# Drive.net
KiCad netlist of a schematic drawn in Altium Designer
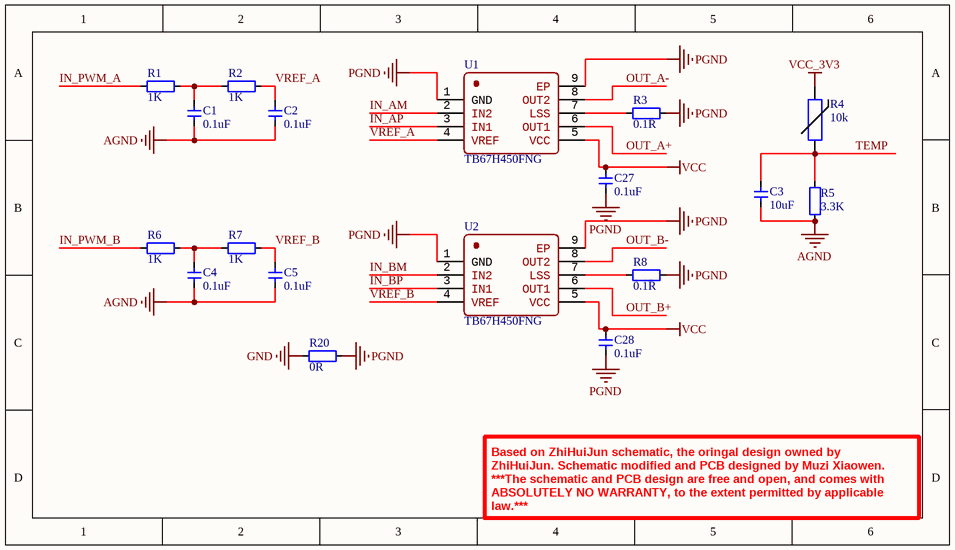
[diagram p0: Drive.SchDoc]

(export (version "E")
  (design (tool "Eeschema 10.0.6"))
  (components
    (comp (ref "C1")
      (value "0.1uF")
      (footprint "motor42-lib:CAP_0402")
      (description "Capacitor")
      (libsource (lib "MyPcbLib") (part "电容-0402"))
    )
    (comp (ref "C2")
      (value "0.1uF")
      (footprint "motor42-lib:CAP_0402")
      (description "Capacitor")
      (libsource (lib "MyPcbLib") (part "电容-0402"))
    )
    (comp (ref "C3")
      (value "10uF")
      (footprint "CAP_0402")
      (description "Capacitor")
      (libsource (lib "MyPcbLib") (part "电容-0402"))
    )
    (comp (ref "C4")
      (value "0.1uF")
      (footprint "motor42-lib:CAP_0402")
      (description "Capacitor")
      (libsource (lib "MyPcbLib") (part "电容-0402"))
    )
    (comp (ref "C5")
      (value "0.1uF")
      (footprint "motor42-lib:CAP_0402")
      (description "Capacitor")
      (libsource (lib "MyPcbLib") (part "电容-0402"))
    )
    (comp (ref "C27")
      (value "0.1uF")
      (footprint "motor42-lib:CAP_0402")
      (description "Capacitor")
      (libsource (lib "MyPcbLib") (part "电容-0402"))
    )
    (comp (ref "C28")
      (value "0.1uF")
      (footprint "motor42-lib:CAP_0402")
      (description "Capacitor")
      (libsource (lib "MyPcbLib") (part "电容-0402"))
    )
    (comp (ref "R1")
      (value "1K")
      (footprint "RES_0402")
      (description "Resistor")
      (libsource (lib "MyPcbLib") (part "电阻-0402"))
    )
    (comp (ref "R2")
      (value "1K")
      (footprint "RES_0402")
      (description "Resistor")
      (libsource (lib "MyPcbLib") (part "电阻-0402"))
    )
    (comp (ref "R3")
      (value "0.1R")
      (footprint "1206-RES")
      (description "Resistor")
      (libsource (lib "MyPcbLib") (part "电阻-1206"))
    )
    (comp (ref "R4")
      (value "10k")
      (footprint "RES_0402")
      (description "THERMISTOR 10K OHM NTC 0402 SMD")
      (fields (field (name "Comment") "NCP15XH103F03RC"))
      (libsource (lib "MyPcbLib") (part "NCP15XH103F03RC"))
    )
    (comp (ref "R5")
      (value "3.3K")
      (footprint "RES_0402")
      (description "Resistor")
      (libsource (lib "") (part "电阻-0402_1"))
    )
    (comp (ref "R6")
      (value "1K")
      (footprint "RES_0402")
      (description "Resistor")
      (libsource (lib "MyPcbLib") (part "电阻-0402"))
    )
    (comp (ref "R7")
      (value "1K")
      (footprint "RES_0402")
      (description "Resistor")
      (libsource (lib "MyPcbLib") (part "电阻-0402"))
    )
    (comp (ref "R8")
      (value "0.1R")
      (footprint "1206-RES")
      (description "Resistor")
      (libsource (lib "MyPcbLib") (part "电阻-1206"))
    )
    (comp (ref "R20")
      (value "0R")
      (footprint "1206-RES")
      (description "Resistor")
      (libsource (lib "MyPcbLib") (part "电阻-1206"))
    )
    (comp (ref "U1")
      (value "TB67H450FNG")
      (footprint "SO-8-PAD")
      (description "PWM Chopper Type DC Brushed Motor Driver")
      (libsource (lib "MyPcbLib") (part "TB67H450FNG"))
    )
    (comp (ref "U2")
      (value "TB67H450FNG")
      (footprint "SO-8-PAD")
      (description "PWM Chopper Type DC Brushed Motor Driver")
      (libsource (lib "MyPcbLib") (part "TB67H450FNG"))
    )
  )
  (nets
    (net (code "1") (name "/IN_AM") (class "Default")
      (node (ref "U1") (pin "2") (pinfunction "IN2_2") (pintype "passive"))
    )
    (net (code "2") (name "/IN_AP") (class "Default")
      (node (ref "U1") (pin "3") (pinfunction "IN1_3") (pintype "passive"))
    )
    (net (code "3") (name "/IN_BM") (class "Default")
      (node (ref "U2") (pin "2") (pinfunction "IN2_2") (pintype "passive"))
    )
    (net (code "4") (name "/IN_BP") (class "Default")
      (node (ref "U2") (pin "3") (pinfunction "IN1_3") (pintype "passive"))
    )
    (net (code "5") (name "/IN_PWM_A") (class "Default")
      (node (ref "R1") (pin "1") (pinfunction "1_1") (pintype "passive"))
    )
    (net (code "6") (name "/IN_PWM_B") (class "Default")
      (node (ref "R6") (pin "1") (pinfunction "1_1") (pintype "passive"))
    )
    (net (code "7") (name "/OUT_A+") (class "Default")
      (node (ref "U1") (pin "6") (pinfunction "OUT1_6") (pintype "passive"))
    )
    (net (code "8") (name "/OUT_A-") (class "Default")
      (node (ref "U1") (pin "8") (pinfunction "OUT2_8") (pintype "passive"))
    )
    (net (code "9") (name "/OUT_B+") (class "Default")
      (node (ref "U2") (pin "6") (pinfunction "OUT1_6") (pintype "passive"))
    )
    (net (code "10") (name "/OUT_B-") (class "Default")
      (node (ref "U2") (pin "8") (pinfunction "OUT2_8") (pintype "passive"))
    )
    (net (code "11") (name "/TEMP") (class "Default")
      (node (ref "C3") (pin "2") (pinfunction "2_2") (pintype "passive"))
      (node (ref "R4") (pin "1") (pinfunction "0_1") (pintype "passive"))
      (node (ref "R5") (pin "2") (pinfunction "2_2") (pintype "passive"))
    )
    (net (code "12") (name "/VREF_A") (class "Default")
      (node (ref "C2") (pin "2") (pinfunction "2_2") (pintype "passive"))
      (node (ref "R2") (pin "2") (pinfunction "2_2") (pintype "passive"))
      (node (ref "U1") (pin "4") (pinfunction "VREF_4") (pintype "passive"))
    )
    (net (code "13") (name "/VREF_B") (class "Default")
      (node (ref "C5") (pin "2") (pinfunction "2_2") (pintype "passive"))
      (node (ref "R7") (pin "2") (pinfunction "2_2") (pintype "passive"))
      (node (ref "U2") (pin "4") (pinfunction "VREF_4") (pintype "passive"))
    )
    (net (code "14") (name "AGND") (class "Default")
      (node (ref "C1") (pin "1") (pinfunction "1_1") (pintype "passive"))
      (node (ref "C2") (pin "1") (pinfunction "1_1") (pintype "passive"))
      (node (ref "C3") (pin "1") (pinfunction "1_1") (pintype "passive"))
      (node (ref "C4") (pin "1") (pinfunction "1_1") (pintype "passive"))
      (node (ref "C5") (pin "1") (pinfunction "1_1") (pintype "passive"))
      (node (ref "R5") (pin "1") (pinfunction "1_1") (pintype "passive"))
    )
    (net (code "15") (name "GND") (class "Default")
      (node (ref "R20") (pin "1") (pinfunction "1_1") (pintype "passive"))
    )
    (net (code "16") (name "Net-(C1-Pad2)") (class "Default")
      (node (ref "C1") (pin "2") (pinfunction "2_2") (pintype "passive"))
      (node (ref "R1") (pin "2") (pinfunction "2_2") (pintype "passive"))
      (node (ref "R2") (pin "1") (pinfunction "1_1") (pintype "passive"))
    )
    (net (code "17") (name "Net-(C4-Pad2)") (class "Default")
      (node (ref "C4") (pin "2") (pinfunction "2_2") (pintype "passive"))
      (node (ref "R6") (pin "2") (pinfunction "2_2") (pintype "passive"))
      (node (ref "R7") (pin "1") (pinfunction "1_1") (pintype "passive"))
    )
    (net (code "18") (name "Net-(U1-LSS)") (class "Default")
      (node (ref "R3") (pin "1") (pinfunction "1_1") (pintype "passive"))
      (node (ref "U1") (pin "7") (pinfunction "LSS_7") (pintype "passive"))
    )
    (net (code "19") (name "Net-(U2-LSS)") (class "Default")
      (node (ref "R8") (pin "1") (pinfunction "1_1") (pintype "passive"))
      (node (ref "U2") (pin "7") (pinfunction "LSS_7") (pintype "passive"))
    )
    (net (code "20") (name "PGND") (class "Default")
      (node (ref "C27") (pin "1") (pinfunction "1_1") (pintype "passive"))
      (node (ref "C28") (pin "1") (pinfunction "1_1") (pintype "passive"))
      (node (ref "R20") (pin "2") (pinfunction "2_2") (pintype "passive"))
      (node (ref "R3") (pin "2") (pinfunction "2_2") (pintype "passive"))
      (node (ref "R8") (pin "2") (pinfunction "2_2") (pintype "passive"))
      (node (ref "U1") (pin "1") (pinfunction "GND_1") (pintype "passive"))
      (node (ref "U1") (pin "9") (pinfunction "EP_9") (pintype "passive"))
      (node (ref "U2") (pin "1") (pinfunction "GND_1") (pintype "passive"))
      (node (ref "U2") (pin "9") (pinfunction "EP_9") (pintype "passive"))
    )
    (net (code "21") (name "VCC") (class "Default")
      (node (ref "C27") (pin "2") (pinfunction "2_2") (pintype "passive"))
      (node (ref "C28") (pin "2") (pinfunction "2_2") (pintype "passive"))
      (node (ref "U1") (pin "5") (pinfunction "VCC_5") (pintype "passive"))
      (node (ref "U2") (pin "5") (pinfunction "VCC_5") (pintype "passive"))
    )
    (net (code "22") (name "VCC_3V3") (class "Default")
      (node (ref "R4") (pin "2") (pinfunction "0_2") (pintype "passive"))
    )
  )
)
